# sap_flux-v10.net
KiCad netlist of a schematic drawn in EAGLE
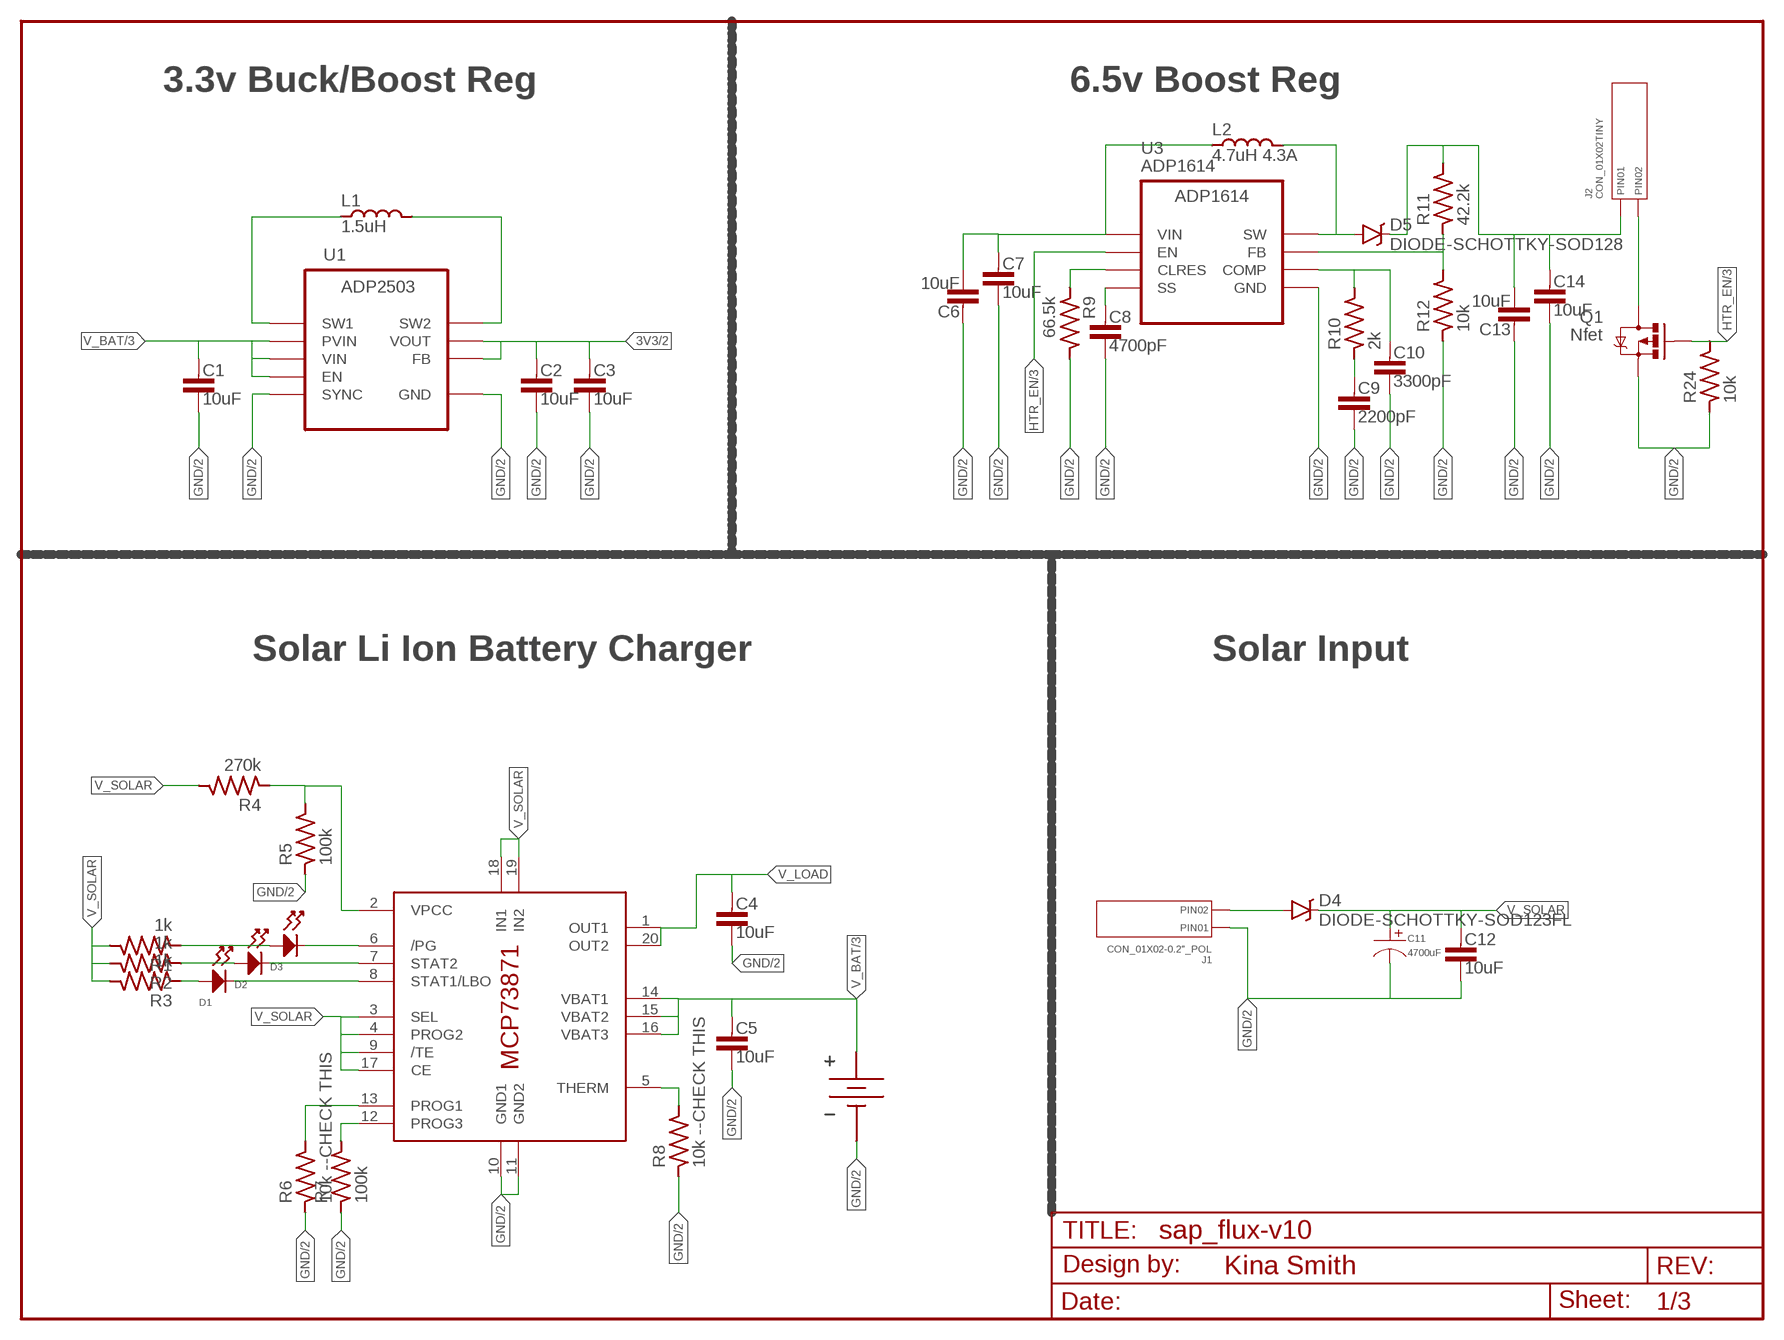
[diagram p0: schematic, sheet 1]
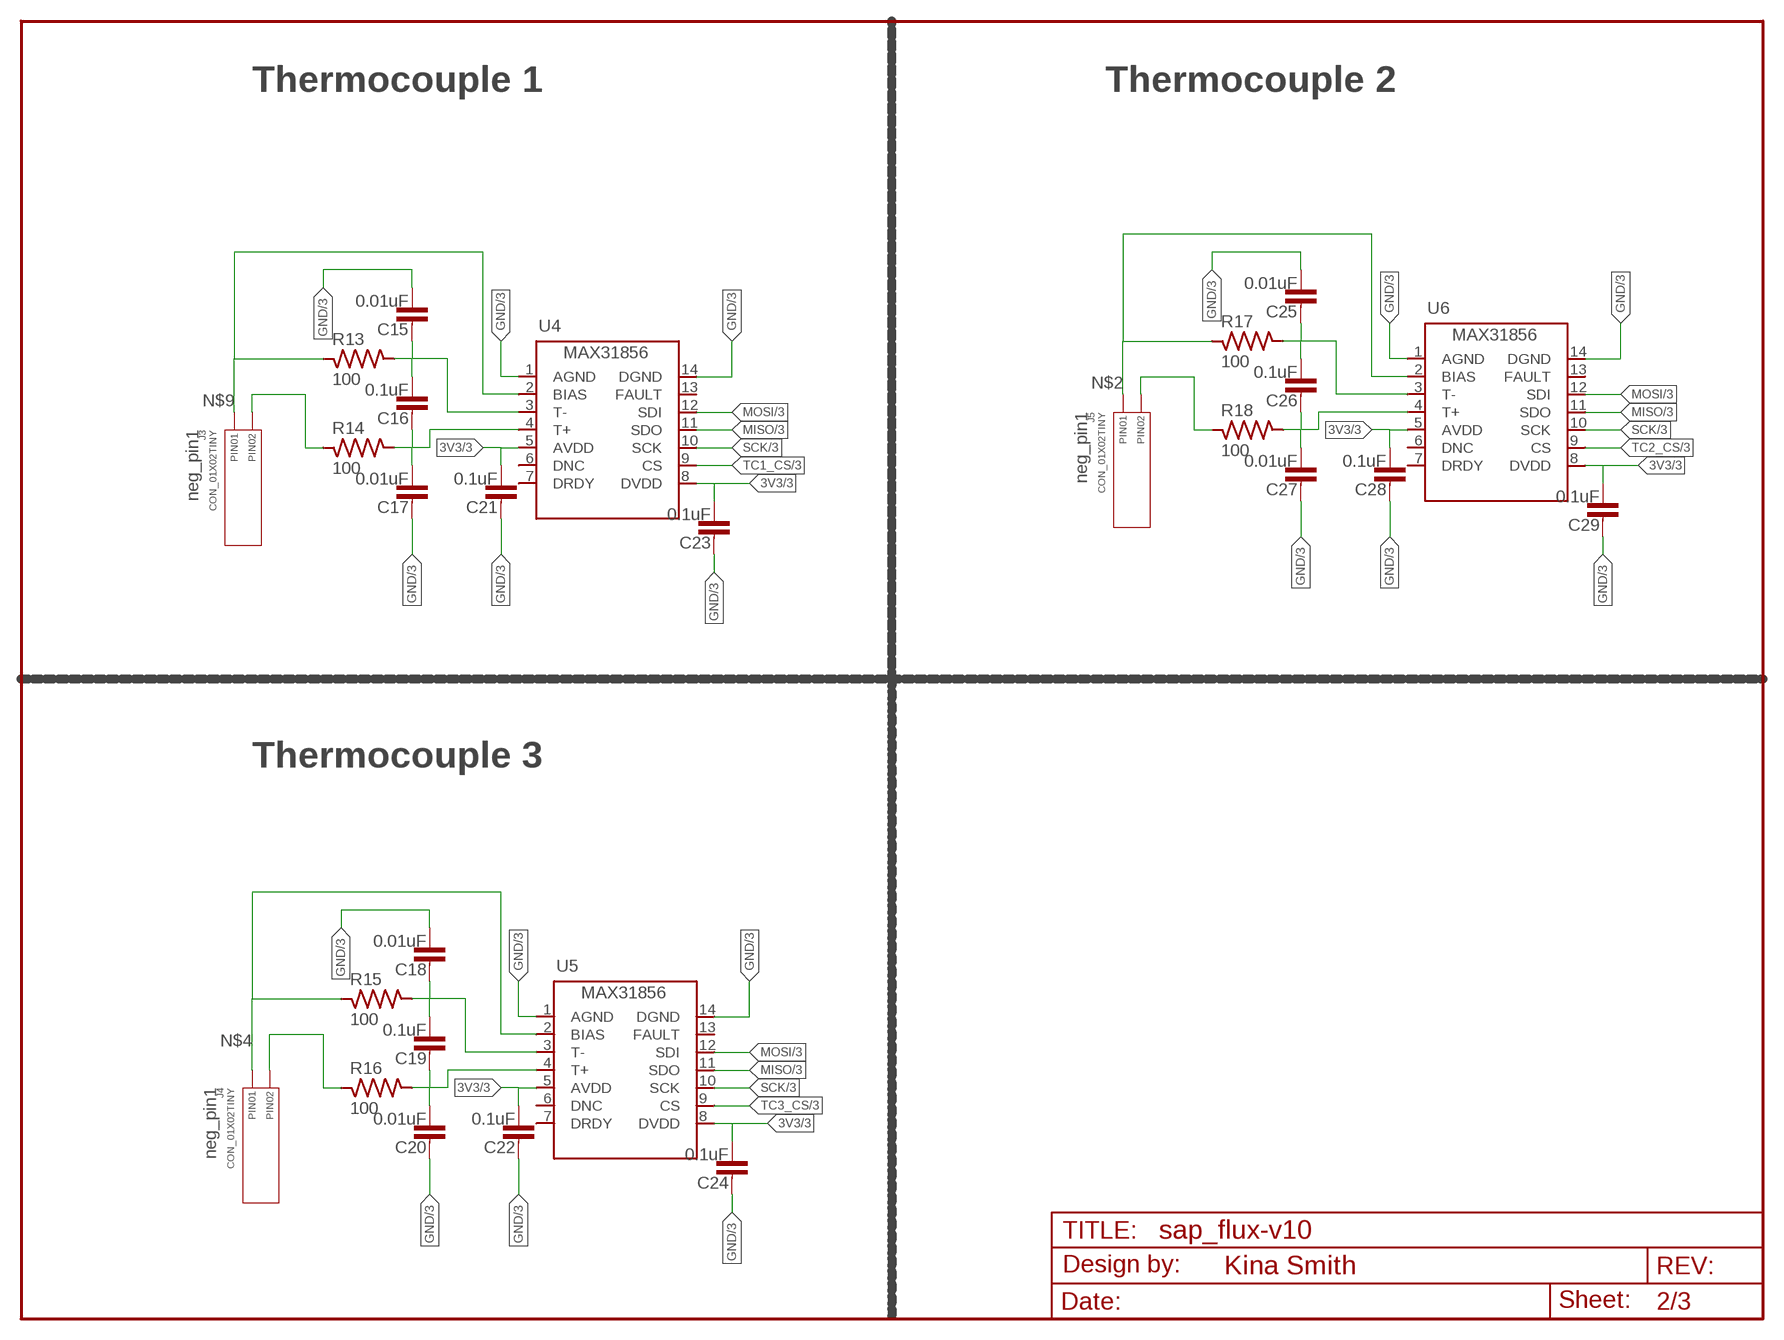
[diagram p1: schematic, sheet 2]
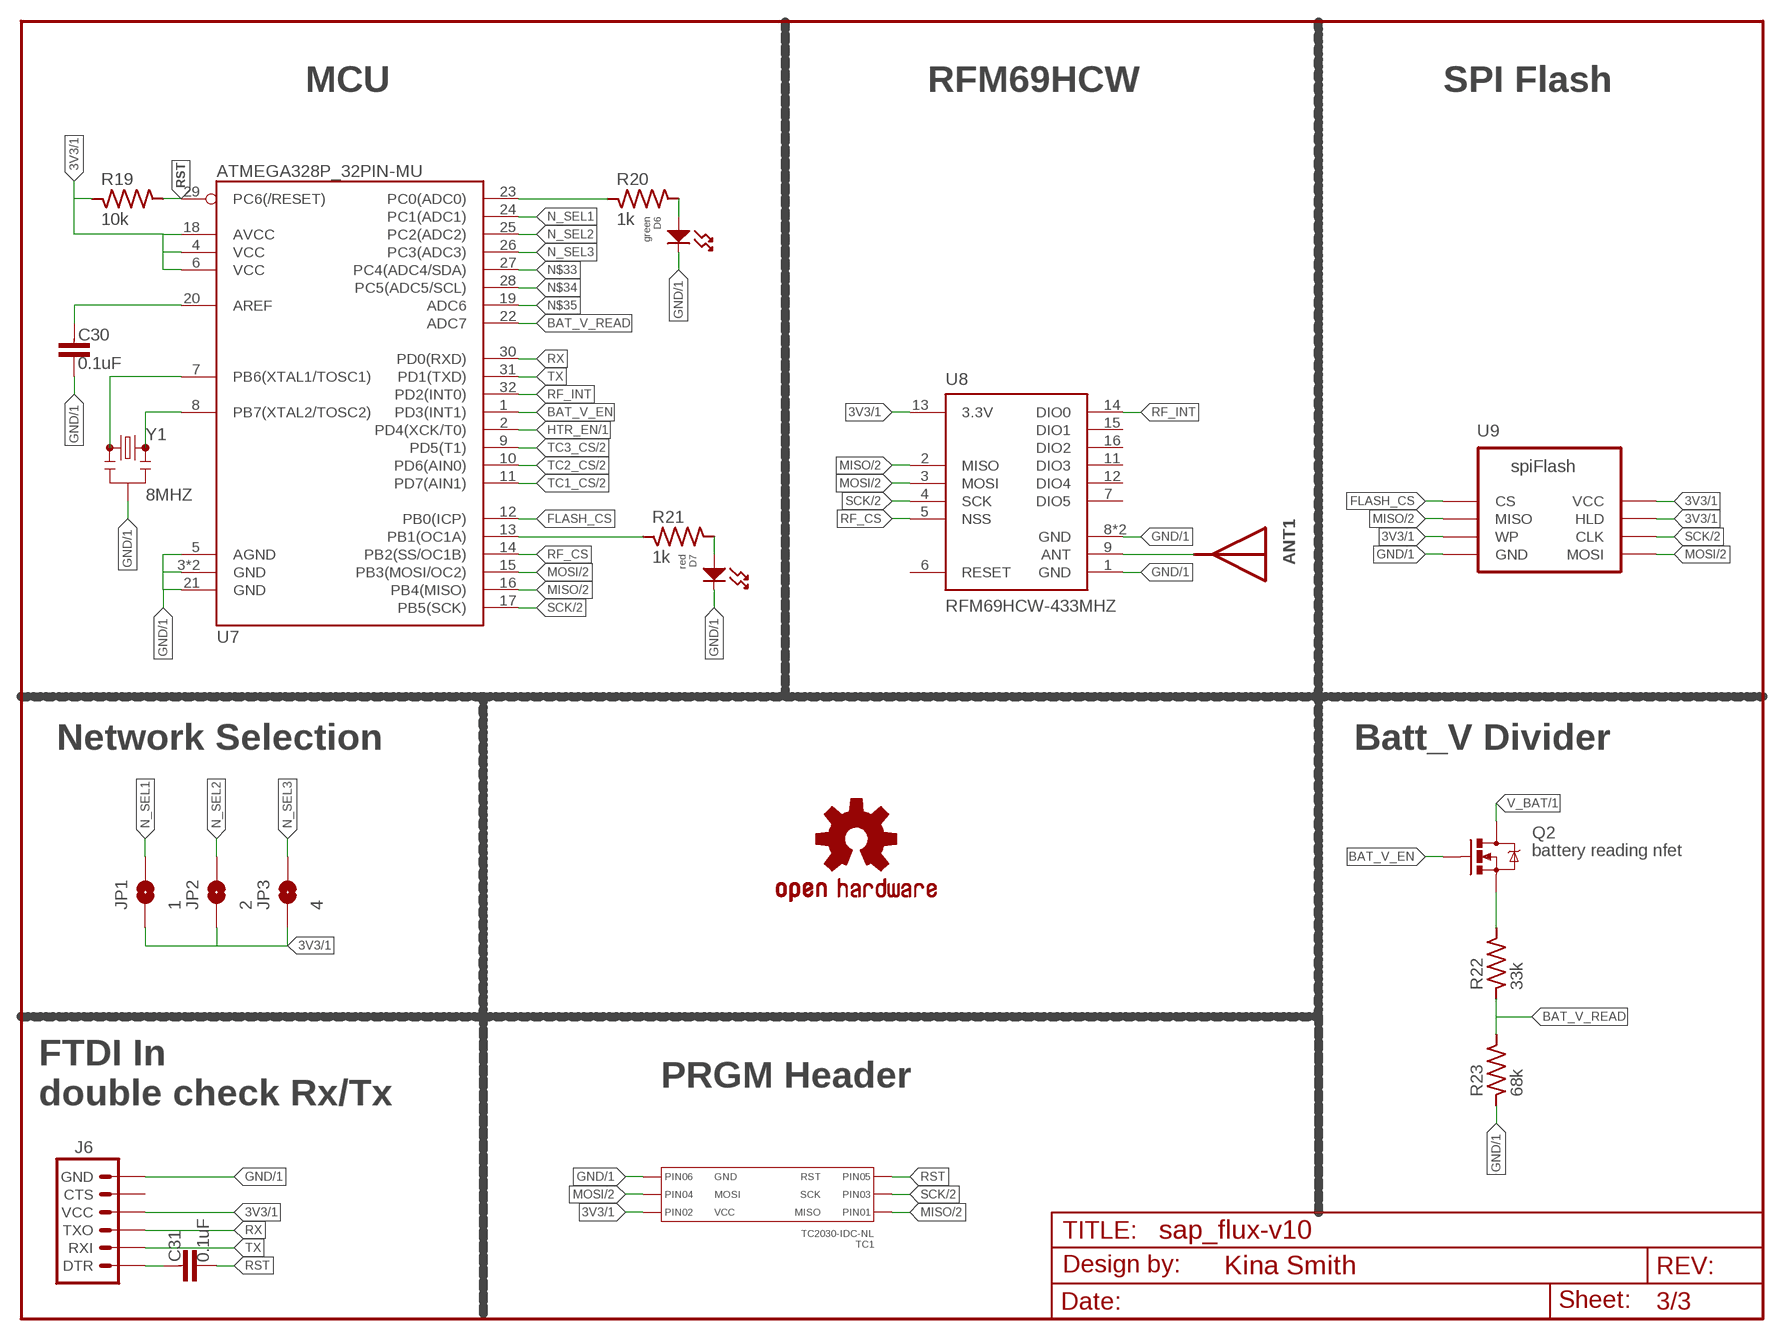
[diagram p2: schematic, sheet 3]

(export (version "E")
  (design (tool "Eeschema 10.0.6"))
  (components
    (comp (ref "ANT1")
      (value "ANTENNA-433_CHIP")
      (footprint "eagle-import:ANT_433_CHIP")
      (fields (field (name "PARTNO") "0433AT62A0020E"))
      (libsource (lib "eagle-import") (part "ANTENNA-433_CHIP"))
    )
    (comp (ref "C30")
      (value "0.1uF")
      (footprint "eagle-import:C0603-N")
      (fields (field (name "PARTNO") "CC0603KRX7R7BB104"))
      (libsource (lib "eagle-import") (part "CAPACITOR_NP0603-N"))
    )
    (comp (ref "C31")
      (value "0.1uF")
      (footprint "eagle-import:C0603-N")
      (fields (field (name "PARTNO") "CC0603KRX7R7BB104"))
      (libsource (lib "eagle-import") (part "CAPACITOR_NP0603-N"))
    )
    (comp (ref "D6")
      (value "green")
      (footprint "eagle-import:LED0603")
      (fields (field (name "HOUSEPART") "NO") (field (name "PARTNO") "LTST-C191KGKT"))
      (libsource (lib "eagle-import") (part "LED_SINGLE-0603"))
    )
    (comp (ref "D7")
      (value "red")
      (footprint "eagle-import:LED0603")
      (fields (field (name "HOUSEPART") "NO") (field (name "PARTNO") "LTST-C191KRKT"))
      (libsource (lib "eagle-import") (part "LED_SINGLE-0603"))
    )
    (comp (ref "FRAME3")
      (value "FRAME-LETTERNO_PACKAGE")
      (footprint "eagle-import:DUMMY")
      (fields (field (name "PARTNO") "NA") (field (name "DESIGNER") "Nobody"))
      (libsource (lib "eagle-import") (part "FRAME-LETTERNO_PACKAGE"))
    )
    (comp (ref "J6")
      (value "ARDUINO_SERIAL_PROGRAMPTH")
      (footprint "eagle-import:1X06")
      (fields (field (name "PARTNO") "68001-106HLF"))
      (libsource (lib "eagle-import") (part "ARDUINO_SERIAL_PROGRAMPTH"))
    )
    (comp (ref "JP1")
      (value "1")
      (footprint "eagle-import:PAD-JUMPER-2-NO_YES_SILK")
      (fields (field (name "PARTNO") "NA"))
      (libsource (lib "eagle-import") (part "JUMPER-PAD-2-NOYES_SILK"))
    )
    (comp (ref "JP2")
      (value "2")
      (footprint "eagle-import:PAD-JUMPER-2-NO_YES_SILK")
      (fields (field (name "PARTNO") "NA"))
      (libsource (lib "eagle-import") (part "JUMPER-PAD-2-NOYES_SILK"))
    )
    (comp (ref "JP3")
      (value "4")
      (footprint "eagle-import:PAD-JUMPER-2-NO_YES_SILK")
      (fields (field (name "PARTNO") "NA"))
      (libsource (lib "eagle-import") (part "JUMPER-PAD-2-NOYES_SILK"))
    )
    (comp (ref "LOGO1")
      (value "OSHW-LOGOS-COPPER")
      (footprint "eagle-import:OSHW-LOGO-S_COPPER")
      (libsource (lib "eagle-import") (part "OSHW-LOGOS-COPPER"))
    )
    (comp (ref "Q2")
      (value "battery reading nfet")
      (footprint "eagle-import:SOT23-3")
      (fields (field (name "PARTNO") "SI2312BDS-T1-GE3"))
      (libsource (lib "eagle-import") (part "MOSFET-NCHANNELSOT23-3"))
    )
    (comp (ref "R19")
      (value "10k")
      (footprint "eagle-import:R0603-N")
      (fields (field (name "PARTNO") "RC0603FR-0710KL"))
      (libsource (lib "eagle-import") (part "RESISTOR0603-N"))
    )
    (comp (ref "R20")
      (value "1k")
      (footprint "eagle-import:R0603-N")
      (fields (field (name "PARTNO") "RC0603FR-071KL"))
      (libsource (lib "eagle-import") (part "RESISTOR0603-N"))
    )
    (comp (ref "R21")
      (value "1k")
      (footprint "eagle-import:R0603-N")
      (fields (field (name "PARTNO") "RC0603FR-071KL"))
      (libsource (lib "eagle-import") (part "RESISTOR0603-N"))
    )
    (comp (ref "R22")
      (value "33k")
      (footprint "eagle-import:R0603-N")
      (fields (field (name "PARTNO") "RC0603FR-0733KL"))
      (libsource (lib "eagle-import") (part "RESISTOR0603-N"))
    )
    (comp (ref "R23")
      (value "68k")
      (footprint "eagle-import:R0603-N")
      (fields (field (name "PARTNO") "RC0603FR-0768KL"))
      (libsource (lib "eagle-import") (part "RESISTOR0603-N"))
    )
    (comp (ref "TC1")
      (value "TC2030-IDC-NL")
      (footprint "eagle-import:TC2030-IDC-NL")
      (fields (field (name "HOUSEPART") "NO") (field (name "PARTNO") "NA"))
      (libsource (lib "eagle-import") (part "CON_02X03_TC2030-IDC-NL_AVRISP"))
    )
    (comp (ref "U7")
      (value "ATMEGA328P_32PIN-MU")
      (footprint "eagle-import:MLF32_RECTPADS")
      (fields (field (name "PARTNO") "ATMEGA328P-MU"))
      (libsource (lib "eagle-import") (part "ATMEGA328P_32PIN-MU"))
    )
    (comp (ref "U8")
      (value "RFM69HCW-433MHZ")
      (footprint "eagle-import:RFM69HCW-XXXS2")
      (fields (field (name "PARTNO") "COM-13910"))
      (libsource (lib "eagle-import") (part "RFM69HCW-433MHZ"))
    )
    (comp (ref "U9")
      (value "WINBOND_FLASH_4MBIT-SOIC")
      (footprint "eagle-import:SOIC8")
      (fields (field (name "PARTNO") "W25X40CLSNIG"))
      (libsource (lib "eagle-import") (part "WINBOND_FLASH_4MBIT-SOIC"))
    )
    (comp (ref "Y1")
      (value "8MHZ")
      (footprint "eagle-import:RESONATOR-SMD")
      (fields (field (name "PARTNO") "CSTCE8M00G55-R0"))
      (libsource (lib "eagle-import") (part "RESONATOR8MHZ"))
    )
    (comp (ref "BATT1")
      (value "BATTERY_HOLDER-18650_CLIP")
      (footprint "eagle-import:BAT_18650_CLIP")
      (fields (field (name "PARTNO") "54"))
      (libsource (lib "eagle-import") (part "BATTERY_HOLDER-18650_CLIP"))
    )
    (comp (ref "C1")
      (value "10uF")
      (footprint "eagle-import:C0805-N")
      (fields (field (name "PARTNO") "GRM21BR61C106KE15K"))
      (libsource (lib "eagle-import") (part "CAPACITOR_NP0805-N"))
    )
    (comp (ref "C2")
      (value "10uF")
      (footprint "eagle-import:C0805-N")
      (fields (field (name "PARTNO") "GRM21BR61C106KE15K"))
      (libsource (lib "eagle-import") (part "CAPACITOR_NP0805-N"))
    )
    (comp (ref "C3")
      (value "10uF")
      (footprint "eagle-import:C0805-N")
      (fields (field (name "PARTNO") "GRM21BR61C106KE15K"))
      (libsource (lib "eagle-import") (part "CAPACITOR_NP0805-N"))
    )
    (comp (ref "C4")
      (value "10uF")
      (footprint "eagle-import:C0805-N")
      (fields (field (name "PARTNO") "GRM21BR61C106KE15K"))
      (libsource (lib "eagle-import") (part "CAPACITOR_NP0805-N"))
    )
    (comp (ref "C5")
      (value "10uF")
      (footprint "eagle-import:C0805-N")
      (fields (field (name "PARTNO") "GRM21BR61C106KE15K"))
      (libsource (lib "eagle-import") (part "CAPACITOR_NP0805-N"))
    )
    (comp (ref "C6")
      (value "10uF")
      (footprint "eagle-import:C0805-N")
      (fields (field (name "PARTNO") "GRM21BR61C106KE15K"))
      (libsource (lib "eagle-import") (part "CAPACITOR_NP0805-N"))
    )
    (comp (ref "C7")
      (value "10uF")
      (footprint "eagle-import:C0805-N")
      (fields (field (name "PARTNO") "GRM21BR61C106KE15K"))
      (libsource (lib "eagle-import") (part "CAPACITOR_NP0805-N"))
    )
    (comp (ref "C8")
      (value "4700pF")
      (footprint "eagle-import:C0603-N")
      (fields (field (name "PARTNO") "GRM188R71C472KA01D"))
      (libsource (lib "eagle-import") (part "CAPACITOR_NP0603-N"))
    )
    (comp (ref "C9")
      (value "2200pF")
      (footprint "eagle-import:C0603-N")
      (fields (field (name "PARTNO") "GRM188R71C222KA01D"))
      (libsource (lib "eagle-import") (part "CAPACITOR_NP0603-N"))
    )
    (comp (ref "C10")
      (value "3300pF")
      (footprint "eagle-import:C0603-N")
      (fields (field (name "PARTNO") "C0603C332K4RACTU"))
      (libsource (lib "eagle-import") (part "CAPACITOR_NP0603-N"))
    )
    (comp (ref "C11")
      (value "4700uF")
      (footprint "eagle-import:CP_TH_5MM")
      (fields (field (name "PARTNO") "ECA-1AM472"))
      (libsource (lib "eagle-import") (part "CAPACITOR_P-TH_5MM"))
    )
    (comp (ref "C12")
      (value "10uF")
      (footprint "eagle-import:C0805-N")
      (fields (field (name "PARTNO") "GRM21BR61C106KE15K"))
      (libsource (lib "eagle-import") (part "CAPACITOR_NP0805-N"))
    )
    (comp (ref "C13")
      (value "10uF")
      (footprint "eagle-import:C0805-N")
      (fields (field (name "PARTNO") "GRM21BR61C106KE15K"))
      (libsource (lib "eagle-import") (part "CAPACITOR_NP0805-N"))
    )
    (comp (ref "C14")
      (value "10uF")
      (footprint "eagle-import:C0805-N")
      (fields (field (name "PARTNO") "GRM21BR61C106KE15K"))
      (libsource (lib "eagle-import") (part "CAPACITOR_NP0805-N"))
    )
    (comp (ref "D1")
      (value "LED_SINGLE-0603")
      (footprint "eagle-import:LED0603")
      (fields (field (name "HOUSEPART") "NO") (field (name "PARTNO") "LTST-C191KRKT"))
      (libsource (lib "eagle-import") (part "LED_SINGLE-0603"))
    )
    (comp (ref "D2")
      (value "LED_SINGLE-0603")
      (footprint "eagle-import:LED0603")
      (fields (field (name "HOUSEPART") "NO") (field (name "PARTNO") "LTST-C191KRKT"))
      (libsource (lib "eagle-import") (part "LED_SINGLE-0603"))
    )
    (comp (ref "D3")
      (value "LED_SINGLE-0603")
      (footprint "eagle-import:LED0603")
      (fields (field (name "HOUSEPART") "NO") (field (name "PARTNO") "LTST-C191KRKT"))
      (libsource (lib "eagle-import") (part "LED_SINGLE-0603"))
    )
    (comp (ref "D4")
      (value "DIODE-SCHOTTKY-SOD123FL")
      (footprint "eagle-import:SOD-123FL")
      (fields (field (name "PARTNO") "MBR120VLSFT1G"))
      (libsource (lib "eagle-import") (part "DIODE-SCHOTTKY-SOD123FL"))
    )
    (comp (ref "D5")
      (value "DIODE-SCHOTTKY-SOD128")
      (footprint "eagle-import:SOD128")
      (fields (field (name "PARTNO") "CMS05(TE12L,Q,M)"))
      (libsource (lib "eagle-import") (part "DIODE-SCHOTTKY-SOD128"))
    )
    (comp (ref "FRAME1")
      (value "FRAME-LETTER")
      (footprint "eagle-import:CREATIVE_COMMONS")
      (fields (field (name "PARTNO") "NA"))
      (libsource (lib "eagle-import") (part "FRAME-LETTER"))
    )
    (comp (ref "J1")
      (value "CON_01X02-0.2\"_POL")
      (footprint "eagle-import:1X02_SCREWTERM_0.2IN")
      (fields (field (name "PARTNO") "0398890042"))
      (libsource (lib "eagle-import") (part "CON_01X02-0.2{dblquote}_POL"))
    )
    (comp (ref "J2")
      (value "CON_01X02TINY")
      (footprint "eagle-import:1X02_TINY")
      (libsource (lib "eagle-import") (part "CON_01X02TINY"))
    )
    (comp (ref "L1")
      (value "1.5uH")
      (footprint "eagle-import:L3030")
      (fields (field (name "PARTNO") "NR3015T1R5N"))
      (libsource (lib "eagle-import") (part "INDUCTOR3030"))
    )
    (comp (ref "L2")
      (value "4.7uH 4.3A")
      (footprint "eagle-import:L8080")
      (fields (field (name "PARTNO") "NRS8040T100MJGJ"))
      (libsource (lib "eagle-import") (part "INDUCTOR8080"))
    )
    (comp (ref "Q1")
      (value "Nfet")
      (footprint "eagle-import:SOT23-3")
      (fields (field (name "PARTNO") "DMN2075U-7"))
      (libsource (lib "eagle-import") (part "MOSFET-PCHANNELSOT23-3"))
    )
    (comp (ref "R1")
      (value "1k")
      (footprint "eagle-import:R0603-N")
      (fields (field (name "PARTNO") "RC0603FR-071KL"))
      (libsource (lib "eagle-import") (part "RESISTOR0603-N"))
    )
    (comp (ref "R2")
      (value "1k")
      (footprint "eagle-import:R0603-N")
      (fields (field (name "PARTNO") "RC0603FR-071KL"))
      (libsource (lib "eagle-import") (part "RESISTOR0603-N"))
    )
    (comp (ref "R3")
      (value "1k")
      (footprint "eagle-import:R0603-N")
      (fields (field (name "PARTNO") "RC0603FR-071KL"))
      (libsource (lib "eagle-import") (part "RESISTOR0603-N"))
    )
    (comp (ref "R4")
      (value "270k")
      (footprint "eagle-import:R0603-N")
      (fields (field (name "PARTNO") "RC0603FR-07270KL"))
      (libsource (lib "eagle-import") (part "RESISTOR0603-N"))
    )
    (comp (ref "R5")
      (value "100k")
      (footprint "eagle-import:R0603-N")
      (fields (field (name "PARTNO") "RC0603FR-07100KL"))
      (libsource (lib "eagle-import") (part "RESISTOR0603-N"))
    )
    (comp (ref "R6")
      (value "10k --CHECK THIS")
      (footprint "eagle-import:R0603-N")
      (fields (field (name "PARTNO") "RC0603FR-0710KL"))
      (libsource (lib "eagle-import") (part "RESISTOR0603-N"))
    )
    (comp (ref "R7")
      (value "100k")
      (footprint "eagle-import:R0603-N")
      (fields (field (name "PARTNO") "RC0603FR-07100KL"))
      (libsource (lib "eagle-import") (part "RESISTOR0603-N"))
    )
    (comp (ref "R8")
      (value "10k --CHECK THIS")
      (footprint "eagle-import:R0603-N")
      (fields (field (name "PARTNO") "RC0603FR-0710KL"))
      (libsource (lib "eagle-import") (part "RESISTOR0603-N"))
    )
    (comp (ref "R9")
      (value "66.5k")
      (footprint "eagle-import:R0603-N")
      (fields (field (name "PARTNO") "RC0603FR-0766K5L"))
      (libsource (lib "eagle-import") (part "RESISTOR0603-N"))
    )
    (comp (ref "R10")
      (value "2k")
      (footprint "eagle-import:R0603-N")
      (fields (field (name "PARTNO") "RC0603FR-072KL"))
      (libsource (lib "eagle-import") (part "RESISTOR0603-N"))
    )
    (comp (ref "R11")
      (value "42.2k")
      (footprint "eagle-import:R0603-N")
      (fields (field (name "PARTNO") "RC0603FR-0742K2L"))
      (libsource (lib "eagle-import") (part "RESISTOR0603-N"))
    )
    (comp (ref "R12")
      (value "10k")
      (footprint "eagle-import:R0603-N")
      (fields (field (name "PARTNO") "RC0603FR-0710KL"))
      (libsource (lib "eagle-import") (part "RESISTOR0603-N"))
    )
    (comp (ref "R24")
      (value "10k")
      (footprint "eagle-import:R0603-N")
      (fields (field (name "PARTNO") "RC0603FR-0710KL"))
      (libsource (lib "eagle-import") (part "RESISTOR0603-N"))
    )
    (comp (ref "U1")
      (value "ADP2503")
      (footprint "eagle-import:DFN300X300X80-11N")
      (fields (field (name "PARTNO") "ADP2503ACPZ-3.3-R7 ") (field (name "PARTNO_1") "ADP2503ACPZ-3.3-R7"))
      (libsource (lib "eagle-import") (part "ADP2503"))
    )
    (comp (ref "U2")
      (value "MCP73871")
      (footprint "eagle-import:QFN20")
      (fields (field (name "PARTNO") "MCP73871-2AAI/ML-ND"))
      (libsource (lib "eagle-import") (part "MCP73871"))
    )
    (comp (ref "U3")
      (value "ADP1614")
      (footprint "eagle-import:DFN300X300X80-11N")
      (fields (field (name "PARTNO") "ADP1614ACPZ-R7") (field (name "PARTNO_1") "ADP1614ACPZ-650-R7"))
      (libsource (lib "eagle-import") (part "ADP1614"))
    )
    (comp (ref "C15")
      (value "0.01uF")
      (footprint "eagle-import:C0603-N")
      (fields (field (name "PARTNO") "GRM188R71C103KA01D"))
      (libsource (lib "eagle-import") (part "CAPACITOR_NP0603-N"))
    )
    (comp (ref "C16")
      (value "0.1uF")
      (footprint "eagle-import:C0603-N")
      (fields (field (name "PARTNO") "CC0603KRX7R7BB104"))
      (libsource (lib "eagle-import") (part "CAPACITOR_NP0603-N"))
    )
    (comp (ref "C17")
      (value "0.01uF")
      (footprint "eagle-import:C0603-N")
      (fields (field (name "PARTNO") "GRM188R71C103KA01D"))
      (libsource (lib "eagle-import") (part "CAPACITOR_NP0603-N"))
    )
    (comp (ref "C18")
      (value "0.01uF")
      (footprint "eagle-import:C0603-N")
      (fields (field (name "PARTNO") "GRM188R71C103KA01D"))
      (libsource (lib "eagle-import") (part "CAPACITOR_NP0603-N"))
    )
    (comp (ref "C19")
      (value "0.1uF")
      (footprint "eagle-import:C0603-N")
      (fields (field (name "PARTNO") "CC0603KRX7R7BB104"))
      (libsource (lib "eagle-import") (part "CAPACITOR_NP0603-N"))
    )
    (comp (ref "C20")
      (value "0.01uF")
      (footprint "eagle-import:C0603-N")
      (fields (field (name "PARTNO") "GRM188R71C103KA01D"))
      (libsource (lib "eagle-import") (part "CAPACITOR_NP0603-N"))
    )
    (comp (ref "C21")
      (value "0.1uF")
      (footprint "eagle-import:C0603-N")
      (fields (field (name "PARTNO") "CC0603KRX7R7BB104"))
      (libsource (lib "eagle-import") (part "CAPACITOR_NP0603-N"))
    )
    (comp (ref "C22")
      (value "0.1uF")
      (footprint "eagle-import:C0603-N")
      (fields (field (name "PARTNO") "CC0603KRX7R7BB104"))
      (libsource (lib "eagle-import") (part "CAPACITOR_NP0603-N"))
    )
    (comp (ref "C23")
      (value "0.1uF")
      (footprint "eagle-import:C0603-N")
      (fields (field (name "PARTNO") "CC0603KRX7R7BB104"))
      (libsource (lib "eagle-import") (part "CAPACITOR_NP0603-N"))
    )
    (comp (ref "C24")
      (value "0.1uF")
      (footprint "eagle-import:C0603-N")
      (fields (field (name "PARTNO") "CC0603KRX7R7BB104"))
      (libsource (lib "eagle-import") (part "CAPACITOR_NP0603-N"))
    )
    (comp (ref "C25")
      (value "0.01uF")
      (footprint "eagle-import:C0603-N")
      (fields (field (name "PARTNO") "GRM188R71C103KA01D"))
      (libsource (lib "eagle-import") (part "CAPACITOR_NP0603-N"))
    )
    (comp (ref "C26")
      (value "0.1uF")
      (footprint "eagle-import:C0603-N")
      (fields (field (name "PARTNO") "CC0603KRX7R7BB104"))
      (libsource (lib "eagle-import") (part "CAPACITOR_NP0603-N"))
    )
    (comp (ref "C27")
      (value "0.01uF")
      (footprint "eagle-import:C0603-N")
      (fields (field (name "PARTNO") "GRM188R71C103KA01D"))
      (libsource (lib "eagle-import") (part "CAPACITOR_NP0603-N"))
    )
    (comp (ref "C28")
      (value "0.1uF")
      (footprint "eagle-import:C0603-N")
      (fields (field (name "PARTNO") "CC0603KRX7R7BB104"))
      (libsource (lib "eagle-import") (part "CAPACITOR_NP0603-N"))
    )
    (comp (ref "C29")
      (value "0.1uF")
      (footprint "eagle-import:C0603-N")
      (fields (field (name "PARTNO") "CC0603KRX7R7BB104"))
      (libsource (lib "eagle-import") (part "CAPACITOR_NP0603-N"))
    )
    (comp (ref "FRAME2")
      (value "FRAME-LETTERNO_PACKAGE")
      (footprint "eagle-import:DUMMY")
      (fields (field (name "PARTNO") "NA") (field (name "DESIGNER") "Nobody"))
      (libsource (lib "eagle-import") (part "FRAME-LETTERNO_PACKAGE"))
    )
    (comp (ref "J3")
      (value "CON_01X02TINY")
      (footprint "eagle-import:1X02_TINY")
      (fields (field (name "NOTE") "neg_pin1"))
      (libsource (lib "eagle-import") (part "CON_01X02TINY"))
    )
    (comp (ref "J4")
      (value "CON_01X02TINY")
      (footprint "eagle-import:1X02_TINY")
      (fields (field (name "NOTE") "neg_pin1"))
      (libsource (lib "eagle-import") (part "CON_01X02TINY"))
    )
    (comp (ref "J5")
      (value "CON_01X02TINY")
      (footprint "eagle-import:1X02_TINY")
      (fields (field (name "NOTE") "neg_pin1"))
      (libsource (lib "eagle-import") (part "CON_01X02TINY"))
    )
    (comp (ref "R13")
      (value "100")
      (footprint "eagle-import:R0603-N")
      (fields (field (name "PARTNO") "RC0603FR-07100RL"))
      (libsource (lib "eagle-import") (part "RESISTOR0603-N"))
    )
    (comp (ref "R14")
      (value "100")
      (footprint "eagle-import:R0603-N")
      (fields (field (name "PARTNO") "RC0603FR-07100RL"))
      (libsource (lib "eagle-import") (part "RESISTOR0603-N"))
    )
    (comp (ref "R15")
      (value "100")
      (footprint "eagle-import:R0603-N")
      (fields (field (name "PARTNO") "RC0603FR-07100RL"))
      (libsource (lib "eagle-import") (part "RESISTOR0603-N"))
    )
    (comp (ref "R16")
      (value "100")
      (footprint "eagle-import:R0603-N")
      (fields (field (name "PARTNO") "RC0603FR-07100RL"))
      (libsource (lib "eagle-import") (part "RESISTOR0603-N"))
    )
    (comp (ref "R17")
      (value "100")
      (footprint "eagle-import:R0603-N")
      (fields (field (name "PARTNO") "RC0603FR-07100RL"))
      (libsource (lib "eagle-import") (part "RESISTOR0603-N"))
    )
    (comp (ref "R18")
      (value "100")
      (footprint "eagle-import:R0603-N")
      (fields (field (name "PARTNO") "RC0603FR-07100RL"))
      (libsource (lib "eagle-import") (part "RESISTOR0603-N"))
    )
    (comp (ref "U4")
      (value "MAX31856MUD+")
      (footprint "eagle-import:TSSOP14")
      (libsource (lib "eagle-import") (part "MAX31856MUD+"))
    )
    (comp (ref "U5")
      (value "MAX31856MUD+")
      (footprint "eagle-import:TSSOP14")
      (libsource (lib "eagle-import") (part "MAX31856MUD+"))
    )
    (comp (ref "U6")
      (value "MAX31856MUD+")
      (footprint "eagle-import:TSSOP14")
      (libsource (lib "eagle-import") (part "MAX31856MUD+"))
    )
  )
  (nets
    (net (code "1") (name "3V3") (class "Default")
      (node (ref "C2") (pin "1") (pinfunction "1_1") (pintype "passive"))
      (node (ref "C21") (pin "2") (pinfunction "2_2") (pintype "passive"))
      (node (ref "C22") (pin "2") (pinfunction "2_2") (pintype "passive"))
      (node (ref "C23") (pin "2") (pinfunction "2_2") (pintype "passive"))
      (node (ref "C24") (pin "2") (pinfunction "2_2") (pintype "passive"))
      (node (ref "C28") (pin "2") (pinfunction "2_2") (pintype "passive"))
      (node (ref "C29") (pin "2") (pinfunction "2_2") (pintype "passive"))
      (node (ref "C3") (pin "1") (pinfunction "1_1") (pintype "passive"))
      (node (ref "J6") (pin "4") (pinfunction "VCC_4") (pintype "passive"))
      (node (ref "JP1") (pin "1") (pinfunction "1_1") (pintype "passive"))
      (node (ref "JP2") (pin "1") (pinfunction "1_1") (pintype "passive"))
      (node (ref "JP3") (pin "1") (pinfunction "1_1") (pintype "passive"))
      (node (ref "R19") (pin "1") (pinfunction "P$1_1") (pintype "passive"))
      (node (ref "TC1") (pin "P$2") (pinfunction "PIN2_P$2") (pintype "bidirectional"))
      (node (ref "U1") (pin "1") (pinfunction "VOUT_1") (pintype "bidirectional"))
      (node (ref "U1") (pin "10") (pinfunction "FB_10") (pintype "bidirectional"))
      (node (ref "U4") (pin "5") (pinfunction "AVDD_5") (pintype "bidirectional"))
      (node (ref "U4") (pin "8") (pinfunction "DVDD_8") (pintype "bidirectional"))
      (node (ref "U5") (pin "5") (pinfunction "AVDD_5") (pintype "bidirectional"))
      (node (ref "U5") (pin "8") (pinfunction "DVDD_8") (pintype "bidirectional"))
      (node (ref "U6") (pin "5") (pinfunction "AVDD_5") (pintype "bidirectional"))
      (node (ref "U6") (pin "8") (pinfunction "DVDD_8") (pintype "bidirectional"))
      (node (ref "U7") (pin "18") (pinfunction "AVCC_18") (pintype "bidirectional"))
      (node (ref "U7") (pin "4") (pinfunction "VCC_4") (pintype "bidirectional"))
      (node (ref "U7") (pin "6") (pinfunction "VCC_6") (pintype "bidirectional"))
      (node (ref "U8") (pin "13") (pinfunction "3.3V_13") (pintype "power_in"))
      (node (ref "U9") (pin "3") (pinfunction "WP_3") (pintype "bidirectional"))
      (node (ref "U9") (pin "7") (pinfunction "HLD_7") (pintype "bidirectional"))
      (node (ref "U9") (pin "8") (pinfunction "VCC_8") (pintype "bidirectional"))
    )
    (net (code "2") (name "BAT_V_EN") (class "Default")
      (node (ref "Q2") (pin "1") (pinfunction "G_1") (pintype "passive"))
      (node (ref "U7") (pin "1") (pinfunction "PD3(INT1)_1") (pintype "bidirectional"))
    )
    (net (code "3") (name "BAT_V_READ") (class "Default")
      (node (ref "R22") (pin "1") (pinfunction "P$1_1") (pintype "passive"))
      (node (ref "R23") (pin "2") (pinfunction "P$2_2") (pintype "passive"))
      (node (ref "U7") (pin "22") (pinfunction "ADC7_22") (pintype "bidirectional"))
    )
    (net (code "4") (name "FLASH_CS") (class "Default")
      (node (ref "U7") (pin "12") (pinfunction "PB0(ICP)_12") (pintype "bidirectional"))
      (node (ref "U9") (pin "1") (pinfunction "CS_1") (pintype "bidirectional"))
    )
    (net (code "5") (name "GND") (class "Default")
      (node (ref "BATT1") (pin "NEG_1") (pinfunction "GND_NEG_1") (pintype "bidirectional"))
      (node (ref "BATT1") (pin "NEG_2") (pinfunction "GND_NEG_2") (pintype "bidirectional"))
      (node (ref "BATT1") (pin "NEG_3") (pinfunction "GND_NEG_3") (pintype "bidirectional"))
      (node (ref "C1") (pin "2") (pinfunction "2_2") (pintype "passive"))
      (node (ref "C10") (pin "2") (pinfunction "2_2") (pintype "passive"))
      (node (ref "C11") (pin "NEG") (pinfunction "NET_NEG") (pintype "passive"))
      (node (ref "C12") (pin "2") (pinfunction "2_2") (pintype "passive"))
      (node (ref "C13") (pin "1") (pinfunction "1_1") (pintype "passive"))
      (node (ref "C14") (pin "2") (pinfunction "2_2") (pintype "passive"))
      (node (ref "C15") (pin "2") (pinfunction "2_2") (pintype "passive"))
      (node (ref "C17") (pin "1") (pinfunction "1_1") (pintype "passive"))
      (node (ref "C18") (pin "2") (pinfunction "2_2") (pintype "passive"))
      (node (ref "C2") (pin "2") (pinfunction "2_2") (pintype "passive"))
      (node (ref "C20") (pin "1") (pinfunction "1_1") (pintype "passive"))
      (node (ref "C21") (pin "1") (pinfunction "1_1") (pintype "passive"))
      (node (ref "C22") (pin "1") (pinfunction "1_1") (pintype "passive"))
      (node (ref "C23") (pin "1") (pinfunction "1_1") (pintype "passive"))
      (node (ref "C24") (pin "1") (pinfunction "1_1") (pintype "passive"))
      (node (ref "C25") (pin "2") (pinfunction "2_2") (pintype "passive"))
      (node (ref "C27") (pin "1") (pinfunction "1_1") (pintype "passive"))
      (node (ref "C28") (pin "1") (pinfunction "1_1") (pintype "passive"))
      (node (ref "C29") (pin "1") (pinfunction "1_1") (pintype "passive"))
      (node (ref "C3") (pin "2") (pinfunction "2_2") (pintype "passive"))
      (node (ref "C30") (pin "2") (pinfunction "2_2") (pintype "passive"))
      (node (ref "C4") (pin "2") (pinfunction "2_2") (pintype "passive"))
      (node (ref "C5") (pin "2") (pinfunction "2_2") (pintype "passive"))
      (node (ref "C6") (pin "1") (pinfunction "1_1") (pintype "passive"))
      (node (ref "C7") (pin "2") (pinfunction "2_2") (pintype "passive"))
      (node (ref "C8") (pin "2") (pinfunction "2_2") (pintype "passive"))
      (node (ref "C9") (pin "2") (pinfunction "2_2") (pintype "passive"))
      (node (ref "D6") (pin "CATHODE") (pinfunction "CATHODE_CATHODE") (pintype "power_in"))
      (node (ref "D7") (pin "CATHODE") (pinfunction "CATHODE_CATHODE") (pintype "power_in"))
      (node (ref "J1") (pin "NEG") (pinfunction "PIN1_NEG") (pintype "bidirectional"))
      (node (ref "J6") (pin "6") (pinfunction "GND_6") (pintype "passive"))
      (node (ref "Q1") (pin "2") (pinfunction "S_2") (pintype "passive"))
      (node (ref "R12") (pin "1") (pinfunction "P$1_1") (pintype "passive"))
      (node (ref "R23") (pin "1") (pinfunction "P$1_1") (pintype "passive"))
      (node (ref "R24") (pin "1") (pinfunction "P$1_1") (pintype "passive"))
      (node (ref "R5") (pin "1") (pinfunction "P$1_1") (pintype "passive"))
      (node (ref "R6") (pin "1") (pinfunction "P$1_1") (pintype "passive"))
      (node (ref "R7") (pin "1") (pinfunction "P$1_1") (pintype "passive"))
      (node (ref "R8") (pin "1") (pinfunction "P$1_1") (pintype "passive"))
      (node (ref "R9") (pin "2") (pinfunction "P$2_2") (pintype "passive"))
      (node (ref "TC1") (pin "P$6") (pinfunction "PIN6_P$6") (pintype "bidirectional"))
      (node (ref "U1") (pin "11") (pinfunction "GND_11") (pintype "bidirectional"))
      (node (ref "U1") (pin "3") (pinfunction "GND_3") (pintype "bidirectional"))
      (node (ref "U1") (pin "7") (pinfunction "SYNC_7") (pintype "bidirectional"))
      (node (ref "U1") (pin "9") (pinfunction "GND_9") (pintype "bidirectional"))
      (node (ref "U2") (pin "10") (pinfunction "GND1_10") (pintype "power_in"))
      (node (ref "U2") (pin "11") (pinfunction "GND2_11") (pintype "power_in"))
      (node (ref "U3") (pin "11") (pinfunction "GND_11") (pintype "bidirectional"))
      (node (ref "U3") (pin "4") (pinfunction "GND_4") (pintype "bidirectional"))
      (node (ref "U3") (pin "5") (pinfunction "GND_5") (pintype "bidirectional"))
      (node (ref "U4") (pin "1") (pinfunction "AGND_1") (pintype "bidirectional"))
      (node (ref "U4") (pin "14") (pinfunction "DGND_14") (pintype "bidirectional"))
      (node (ref "U5") (pin "1") (pinfunction "AGND_1") (pintype "bidirectional"))
      (node (ref "U5") (pin "14") (pinfunction "DGND_14") (pintype "bidirectional"))
      (node (ref "U6") (pin "1") (pinfunction "AGND_1") (pintype "bidirectional"))
      (node (ref "U6") (pin "14") (pinfunction "DGND_14") (pintype "bidirectional"))
      (node (ref "U7") (pin "21") (pinfunction "GND_21") (pintype "bidirectional"))
      (node (ref "U7") (pin "3") (pinfunction "GND_3") (pintype "bidirectional"))
      (node (ref "U7") (pin "5") (pinfunction "AGND_5") (pintype "bidirectional"))
      (node (ref "U7") (pin "PAD") (pinfunction "GND_PAD") (pintype "bidirectional"))
      (node (ref "U8") (pin "1") (pinfunction "GND_1") (pintype "power_in"))
      (node (ref "U8") (pin "10") (pinfunction "GND_10") (pintype "power_in"))
      (node (ref "U8") (pin "8") (pinfunction "GND_8") (pintype "power_in"))
      (node (ref "U9") (pin "4") (pinfunction "GND_4") (pintype "bidirectional"))
      (node (ref "Y1") (pin "2") (pinfunction "2_2") (pintype "passive"))
    )
    (net (code "6") (name "HTR_EN") (class "Default")
      (node (ref "Q1") (pin "1") (pinfunction "G_1") (pintype "passive"))
      (node (ref "R24") (pin "2") (pinfunction "P$2_2") (pintype "passive"))
      (node (ref "U3") (pin "3") (pinfunction "EN_3") (pintype "bidirectional"))
      (node (ref "U7") (pin "2") (pinfunction "PD4(XCK/T0)_2") (pintype "bidirectional"))
    )
    (net (code "7") (name "MISO") (class "Default")
      (node (ref "TC1") (pin "P$1") (pinfunction "PIN1_P$1") (pintype "bidirectional"))
      (node (ref "U4") (pin "11") (pinfunction "SDO_11") (pintype "bidirectional"))
      (node (ref "U5") (pin "11") (pinfunction "SDO_11") (pintype "bidirectional"))
      (node (ref "U6") (pin "11") (pinfunction "SDO_11") (pintype "bidirectional"))
      (node (ref "U7") (pin "16") (pinfunction "PB4(MISO)_16") (pintype "bidirectional"))
      (node (ref "U8") (pin "2") (pinfunction "MISO_2") (pintype "bidirectional"))
      (node (ref "U9") (pin "2") (pinfunction "MISO_2") (pintype "bidirectional"))
    )
    (net (code "8") (name "MOSI") (class "Default")
      (node (ref "TC1") (pin "P$4") (pinfunction "PIN4_P$4") (pintype "bidirectional"))
      (node (ref "U4") (pin "12") (pinfunction "SDI_12") (pintype "bidirectional"))
      (node (ref "U5") (pin "12") (pinfunction "SDI_12") (pintype "bidirectional"))
      (node (ref "U6") (pin "12") (pinfunction "SDI_12") (pintype "bidirectional"))
      (node (ref "U7") (pin "15") (pinfunction "PB3(MOSI/OC2)_15") (pintype "bidirectional"))
      (node (ref "U8") (pin "3") (pinfunction "MOSI_3") (pintype "input"))
      (node (ref "U9") (pin "5") (pinfunction "MOSI_5") (pintype "bidirectional"))
    )
    (net (code "9") (name "N$2") (class "Default")
      (node (ref "J5") (pin "NEG") (pinfunction "PIN1_NEG") (pintype "bidirectional"))
      (node (ref "R17") (pin "1") (pinfunction "P$1_1") (pintype "passive"))
      (node (ref "U6") (pin "2") (pinfunction "BIAS_2") (pintype "bidirectional"))
    )
    (net (code "10") (name "N$4") (class "Default")
      (node (ref "J4") (pin "NEG") (pinfunction "PIN1_NEG") (pintype "bidirectional"))
      (node (ref "R15") (pin "1") (pinfunction "P$1_1") (pintype "passive"))
      (node (ref "U5") (pin "2") (pinfunction "BIAS_2") (pintype "bidirectional"))
    )
    (net (code "11") (name "N$9") (class "Default")
      (node (ref "J3") (pin "NEG") (pinfunction "PIN1_NEG") (pintype "bidirectional"))
      (node (ref "R13") (pin "1") (pinfunction "P$1_1") (pintype "passive"))
      (node (ref "U4") (pin "2") (pinfunction "BIAS_2") (pintype "bidirectional"))
    )
    (net (code "12") (name "N$33") (class "Default")
      (node (ref "U7") (pin "27") (pinfunction "PC4(ADC4/SDA)_27") (pintype "bidirectional"))
    )
    (net (code "13") (name "N$34") (class "Default")
      (node (ref "U7") (pin "28") (pinfunction "PC5(ADC5/SCL)_28") (pintype "bidirectional"))
    )
    (net (code "14") (name "N$35") (class "Default")
      (node (ref "U7") (pin "19") (pinfunction "ADC6_19") (pintype "bidirectional"))
    )
    (net (code "15") (name "N_SEL1") (class "Default")
      (node (ref "JP1") (pin "2") (pinfunction "2_2") (pintype "passive"))
      (node (ref "U7") (pin "24") (pinfunction "PC1(ADC1)_24") (pintype "bidirectional"))
    )
    (net (code "16") (name "N_SEL2") (class "Default")
      (node (ref "JP2") (pin "2") (pinfunction "2_2") (pintype "passive"))
      (node (ref "U7") (pin "25") (pinfunction "PC2(ADC2)_25") (pintype "bidirectional"))
    )
    (net (code "17") (name "N_SEL3") (class "Default")
      (node (ref "JP3") (pin "2") (pinfunction "2_2") (pintype "passive"))
      (node (ref "U7") (pin "26") (pinfunction "PC3(ADC3)_26") (pintype "bidirectional"))
    )
    (net (code "18") (name "Net-(D5-A)") (class "Default")
      (node (ref "D5") (pin "A-2") (pinfunction "A_A-2") (pintype "passive"))
      (node (ref "L2") (pin "2") (pinfunction "P$2_2") (pintype "passive"))
      (node (ref "U3") (pin "6") (pinfunction "SW_6") (pintype "bidirectional"))
      (node (ref "U3") (pin "7") (pinfunction "SW_7") (pintype "bidirectional"))
    )
    (net (code "19") (name "Net-(D5-C)") (class "Default")
      (node (ref "C13") (pin "2") (pinfunction "2_2") (pintype "passive"))
      (node (ref "C14") (pin "1") (pinfunction "1_1") (pintype "passive"))
      (node (ref "D5") (pin "C-1") (pinfunction "C_C-1") (pintype "passive"))
      (node (ref "J2") (pin "NEG") (pinfunction "PIN1_NEG") (pintype "bidirectional"))
      (node (ref "R11") (pin "2") (pinfunction "P$2_2") (pintype "passive"))
    )
    (net (code "20") (name "Net-(J1-PIN2)") (class "Default")
      (node (ref "D4") (pin "A") (pinfunction "A_A") (pintype "passive"))
      (node (ref "J1") (pin "POS") (pinfunction "PIN2_POS") (pintype "bidirectional"))
    )
    (net (code "21") (name "Net-(J2-PIN2)") (class "Default")
      (node (ref "J2") (pin "POS") (pinfunction "PIN2_POS") (pintype "bidirectional"))
      (node (ref "Q1") (pin "3") (pinfunction "D_3") (pintype "passive"))
    )
    (net (code "22") (name "Net-(J3-PIN2)") (class "Default")
      (node (ref "J3") (pin "POS") (pinfunction "PIN2_POS") (pintype "bidirectional"))
      (node (ref "R14") (pin "1") (pinfunction "P$1_1") (pintype "passive"))
    )
    (net (code "23") (name "Net-(J4-PIN2)") (class "Default")
      (node (ref "J4") (pin "POS") (pinfunction "PIN2_POS") (pintype "bidirectional"))
      (node (ref "R16") (pin "1") (pinfunction "P$1_1") (pintype "passive"))
    )
    (net (code "24") (name "Net-(J5-PIN2)") (class "Default")
      (node (ref "J5") (pin "POS") (pinfunction "PIN2_POS") (pintype "bidirectional"))
      (node (ref "R18") (pin "1") (pinfunction "P$1_1") (pintype "passive"))
    )
    (net (code "25") (name "Net-(J6-DTR)") (class "Default")
      (node (ref "C31") (pin "1") (pinfunction "1_1") (pintype "passive"))
      (node (ref "J6") (pin "1") (pinfunction "DTR_1") (pintype "passive"))
    )
    (net (code "26") (name "Net-(Q2-S)") (class "Default")
      (node (ref "Q2") (pin "2") (pinfunction "S_2") (pintype "passive"))
      (node (ref "R22") (pin "2") (pinfunction "P$2_2") (pintype "passive"))
    )
    (net (code "27") (name "Net-(R1-P$1)") (class "Default")
      (node (ref "D3") (pin "ANODE") (pinfunction "ANODE_ANODE") (pintype "power_in"))
      (node (ref "R1") (pin "1") (pinfunction "P$1_1") (pintype "passive"))
    )
    (net (code "28") (name "Net-(R2-P$1)") (class "Default")
      (node (ref "D2") (pin "ANODE") (pinfunction "ANODE_ANODE") (pintype "power_in"))
      (node (ref "R2") (pin "1") (pinfunction "P$1_1") (pintype "passive"))
    )
    (net (code "29") (name "Net-(R3-P$1)") (class "Default")
      (node (ref "D1") (pin "ANODE") (pinfunction "ANODE_ANODE") (pintype "power_in"))
      (node (ref "R3") (pin "1") (pinfunction "P$1_1") (pintype "passive"))
    )
    (net (code "30") (name "Net-(R4-P$1)") (class "Default")
      (node (ref "R4") (pin "1") (pinfunction "P$1_1") (pintype "passive"))
      (node (ref "R5") (pin "2") (pinfunction "P$2_2") (pintype "passive"))
      (node (ref "U2") (pin "2") (pinfunction "VPCC_2") (pintype "input"))
    )
    (net (code "31") (name "Net-(R6-P$2)") (class "Default")
      (node (ref "R6") (pin "2") (pinfunction "P$2_2") (pintype "passive"))
      (node (ref "U2") (pin "13") (pinfunction "PROG1_13") (pintype "input"))
    )
    (net (code "32") (name "Net-(R7-P$2)") (class "Default")
      (node (ref "R7") (pin "2") (pinfunction "P$2_2") (pintype "passive"))
      (node (ref "U2") (pin "12") (pinfunction "PROG3_12") (pintype "input"))
    )
    (net (code "33") (name "Net-(R8-P$2)") (class "Default")
      (node (ref "R8") (pin "2") (pinfunction "P$2_2") (pintype "passive"))
      (node (ref "U2") (pin "5") (pinfunction "THERM_5") (pintype "input"))
    )
    (net (code "34") (name "Net-(R9-P$1)") (class "Default")
      (node (ref "R9") (pin "1") (pinfunction "P$1_1") (pintype "passive"))
      (node (ref "U3") (pin "9") (pinfunction "CLRES_9") (pintype "bidirectional"))
    )
    (net (code "35") (name "Net-(R10-P$1)") (class "Default")
      (node (ref "C9") (pin "1") (pinfunction "1_1") (pintype "passive"))
      (node (ref "R10") (pin "1") (pinfunction "P$1_1") (pintype "passive"))
    )
    (net (code "36") (name "Net-(R10-P$2)") (class "Default")
      (node (ref "C10") (pin "1") (pinfunction "1_1") (pintype "passive"))
      (node (ref "R10") (pin "2") (pinfunction "P$2_2") (pintype "passive"))
      (node (ref "U3") (pin "1") (pinfunction "COMP_1") (pintype "bidirectional"))
    )
    (net (code "37") (name "Net-(R11-P$1)") (class "Default")
      (node (ref "R11") (pin "1") (pinfunction "P$1_1") (pintype "passive"))
      (node (ref "R12") (pin "2") (pinfunction "P$2_2") (pintype "passive"))
      (node (ref "U3") (pin "2") (pinfunction "FB_2") (pintype "bidirectional"))
    )
    (net (code "38") (name "Net-(R13-P$2)") (class "Default")
      (node (ref "C15") (pin "1") (pinfunction "1_1") (pintype "passive"))
      (node (ref "C16") (pin "2") (pinfunction "2_2") (pintype "passive"))
      (node (ref "R13") (pin "2") (pinfunction "P$2_2") (pintype "passive"))
      (node (ref "U4") (pin "3") (pinfunction "T-_3") (pintype "bidirectional"))
    )
    (net (code "39") (name "Net-(R14-P$2)") (class "Default")
      (node (ref "C16") (pin "1") (pinfunction "1_1") (pintype "passive"))
      (node (ref "C17") (pin "2") (pinfunction "2_2") (pintype "passive"))
      (node (ref "R14") (pin "2") (pinfunction "P$2_2") (pintype "passive"))
      (node (ref "U4") (pin "4") (pinfunction "T+_4") (pintype "bidirectional"))
    )
    (net (code "40") (name "Net-(R15-P$2)") (class "Default")
      (node (ref "C18") (pin "1") (pinfunction "1_1") (pintype "passive"))
      (node (ref "C19") (pin "2") (pinfunction "2_2") (pintype "passive"))
      (node (ref "R15") (pin "2") (pinfunction "P$2_2") (pintype "passive"))
      (node (ref "U5") (pin "3") (pinfunction "T-_3") (pintype "bidirectional"))
    )
    (net (code "41") (name "Net-(R16-P$2)") (class "Default")
      (node (ref "C19") (pin "1") (pinfunction "1_1") (pintype "passive"))
      (node (ref "C20") (pin "2") (pinfunction "2_2") (pintype "passive"))
      (node (ref "R16") (pin "2") (pinfunction "P$2_2") (pintype "passive"))
      (node (ref "U5") (pin "4") (pinfunction "T+_4") (pintype "bidirectional"))
    )
    (net (code "42") (name "Net-(R17-P$2)") (class "Default")
      (node (ref "C25") (pin "1") (pinfunction "1_1") (pintype "passive"))
      (node (ref "C26") (pin "2") (pinfunction "2_2") (pintype "passive"))
      (node (ref "R17") (pin "2") (pinfunction "P$2_2") (pintype "passive"))
      (node (ref "U6") (pin "3") (pinfunction "T-_3") (pintype "bidirectional"))
    )
    (net (code "43") (name "Net-(R18-P$2)") (class "Default")
      (node (ref "C26") (pin "1") (pinfunction "1_1") (pintype "passive"))
      (node (ref "C27") (pin "2") (pinfunction "2_2") (pintype "passive"))
      (node (ref "R18") (pin "2") (pinfunction "P$2_2") (pintype "passive"))
      (node (ref "U6") (pin "4") (pinfunction "T+_4") (pintype "bidirectional"))
    )
    (net (code "44") (name "Net-(R20-P$1)") (class "Default")
      (node (ref "R20") (pin "1") (pinfunction "P$1_1") (pintype "passive"))
      (node (ref "U7") (pin "23") (pinfunction "PC0(ADC0)_23") (pintype "bidirectional"))
    )
    (net (code "45") (name "Net-(R20-P$2)") (class "Default")
      (node (ref "D6") (pin "ANODE") (pinfunction "ANODE_ANODE") (pintype "power_in"))
      (node (ref "R20") (pin "2") (pinfunction "P$2_2") (pintype "passive"))
    )
    (net (code "46") (name "Net-(R21-P$1)") (class "Default")
      (node (ref "R21") (pin "1") (pinfunction "P$1_1") (pintype "passive"))
      (node (ref "U7") (pin "13") (pinfunction "PB1(OC1A)_13") (pintype "bidirectional"))
    )
    (net (code "47") (name "Net-(R21-P$2)") (class "Default")
      (node (ref "D7") (pin "ANODE") (pinfunction "ANODE_ANODE") (pintype "power_in"))
      (node (ref "R21") (pin "2") (pinfunction "P$2_2") (pintype "passive"))
    )
    (net (code "48") (name "Net-(U1-SW1)") (class "Default")
      (node (ref "L1") (pin "P$1") (pinfunction "P$1_P$1") (pintype "passive"))
      (node (ref "U1") (pin "4") (pinfunction "SW1_4") (pintype "bidirectional"))
    )
    (net (code "49") (name "Net-(U1-SW2)") (class "Default")
      (node (ref "L1") (pin "P$2") (pinfunction "P$2_P$2") (pintype "passive"))
      (node (ref "U1") (pin "2") (pinfunction "SW2_2") (pintype "bidirectional"))
    )
    (net (code "50") (name "Net-(U2-STAT1{slash}LBO)") (class "Default")
      (node (ref "D1") (pin "CATHODE") (pinfunction "CATHODE_CATHODE") (pintype "power_in"))
      (node (ref "U2") (pin "8") (pinfunction "STAT1/LBO_8") (pintype "output"))
    )
    (net (code "51") (name "Net-(U2-STAT2)") (class "Default")
      (node (ref "D2") (pin "CATHODE") (pinfunction "CATHODE_CATHODE") (pintype "power_in"))
      (node (ref "U2") (pin "7") (pinfunction "STAT2_7") (pintype "output"))
    )
    (net (code "52") (name "Net-(U2-{slash}PG)") (class "Default")
      (node (ref "D3") (pin "CATHODE") (pinfunction "CATHODE_CATHODE") (pintype "power_in"))
      (node (ref "U2") (pin "6") (pinfunction "/PG_6") (pintype "output"))
    )
    (net (code "53") (name "Net-(U3-SS)") (class "Default")
      (node (ref "C8") (pin "1") (pinfunction "1_1") (pintype "passive"))
      (node (ref "U3") (pin "10") (pinfunction "SS_10") (pintype "bidirectional"))
    )
    (net (code "54") (name "Net-(U7-AREF)") (class "Default")
      (node (ref "C30") (pin "1") (pinfunction "1_1") (pintype "passive"))
      (node (ref "U7") (pin "20") (pinfunction "AREF_20") (pintype "bidirectional"))
    )
    (net (code "55") (name "Net-(U7-PB6(XTAL1{slash}TOSC1))") (class "Default")
      (node (ref "U7") (pin "7") (pinfunction "PB6(XTAL1/TOSC1)_7") (pintype "bidirectional"))
      (node (ref "Y1") (pin "1") (pinfunction "1_1") (pintype "passive"))
    )
    (net (code "56") (name "Net-(U7-PB7(XTAL2{slash}TOSC2))") (class "Default")
      (node (ref "U7") (pin "8") (pinfunction "PB7(XTAL2/TOSC2)_8") (pintype "bidirectional"))
      (node (ref "Y1") (pin "3") (pinfunction "3_3") (pintype "passive"))
    )
    (net (code "57") (name "Net-(U8-ANT)") (class "Default")
      (node (ref "ANT1") (pin "1") (pinfunction "1_1") (pintype "bidirectional"))
      (node (ref "U8") (pin "9") (pinfunction "ANT_9") (pintype "passive"))
    )
    (net (code "58") (name "RF_CS") (class "Default")
      (node (ref "U7") (pin "14") (pinfunction "PB2(SS/OC1B)_14") (pintype "bidirectional"))
      (node (ref "U8") (pin "5") (pinfunction "NSS_5") (pintype "input"))
    )
    (net (code "59") (name "RF_INT") (class "Default")
      (node (ref "U7") (pin "32") (pinfunction "PD2(INT0)_32") (pintype "bidirectional"))
      (node (ref "U8") (pin "14") (pinfunction "DIO0_14") (pintype "bidirectional"))
    )
    (net (code "60") (name "RST") (class "Default")
      (node (ref "C31") (pin "2") (pinfunction "2_2") (pintype "passive"))
      (node (ref "R19") (pin "2") (pinfunction "P$2_2") (pintype "passive"))
      (node (ref "TC1") (pin "P$5") (pinfunction "PIN5_P$5") (pintype "bidirectional"))
      (node (ref "U7") (pin "29") (pinfunction "PC6(/RESET)_29") (pintype "bidirectional"))
    )
    (net (code "61") (name "RX") (class "Default")
      (node (ref "J6") (pin "3") (pinfunction "TXO_3") (pintype "passive"))
      (node (ref "U7") (pin "30") (pinfunction "PD0(RXD)_30") (pintype "bidirectional"))
    )
    (net (code "62") (name "SCK") (class "Default")
      (node (ref "TC1") (pin "P$3") (pinfunction "PIN3_P$3") (pintype "bidirectional"))
      (node (ref "U4") (pin "10") (pinfunction "SCK_10") (pintype "bidirectional"))
      (node (ref "U5") (pin "10") (pinfunction "SCK_10") (pintype "bidirectional"))
      (node (ref "U6") (pin "10") (pinfunction "SCK_10") (pintype "bidirectional"))
      (node (ref "U7") (pin "17") (pinfunction "PB5(SCK)_17") (pintype "bidirectional"))
      (node (ref "U8") (pin "4") (pinfunction "SCK_4") (pintype "input"))
      (node (ref "U9") (pin "6") (pinfunction "CLK_6") (pintype "bidirectional"))
    )
    (net (code "63") (name "TC1_CS") (class "Default")
      (node (ref "U4") (pin "9") (pinfunction "CS_9") (pintype "bidirectional"))
      (node (ref "U7") (pin "11") (pinfunction "PD7(AIN1)_11") (pintype "bidirectional"))
    )
    (net (code "64") (name "TC2_CS") (class "Default")
      (node (ref "U6") (pin "9") (pinfunction "CS_9") (pintype "bidirectional"))
      (node (ref "U7") (pin "10") (pinfunction "PD6(AIN0)_10") (pintype "bidirectional"))
    )
    (net (code "65") (name "TC3_CS") (class "Default")
      (node (ref "U5") (pin "9") (pinfunction "CS_9") (pintype "bidirectional"))
      (node (ref "U7") (pin "9") (pinfunction "PD5(T1)_9") (pintype "bidirectional"))
    )
    (net (code "66") (name "TX") (class "Default")
      (node (ref "J6") (pin "2") (pinfunction "RXI_2") (pintype "passive"))
      (node (ref "U7") (pin "31") (pinfunction "PD1(TXD)_31") (pintype "bidirectional"))
    )
    (net (code "67") (name "V_BAT") (class "Default")
      (node (ref "BATT1") (pin "POS_1") (pinfunction "VBAT_POS_1") (pintype "bidirectional"))
      (node (ref "BATT1") (pin "POS_2") (pinfunction "VBAT_POS_2") (pintype "bidirectional"))
      (node (ref "BATT1") (pin "POS_3") (pinfunction "VBAT_POS_3") (pintype "bidirectional"))
      (node (ref "C1") (pin "1") (pinfunction "1_1") (pintype "passive"))
      (node (ref "C5") (pin "1") (pinfunction "1_1") (pintype "passive"))
      (node (ref "C6") (pin "2") (pinfunction "2_2") (pintype "passive"))
      (node (ref "C7") (pin "1") (pinfunction "1_1") (pintype "passive"))
      (node (ref "L2") (pin "1") (pinfunction "P$1_1") (pintype "passive"))
      (node (ref "Q2") (pin "3") (pinfunction "D_3") (pintype "passive"))
      (node (ref "U1") (pin "5") (pinfunction "PVIN_5") (pintype "bidirectional"))
      (node (ref "U1") (pin "6") (pinfunction "EN_6") (pintype "bidirectional"))
      (node (ref "U1") (pin "8") (pinfunction "VIN_8") (pintype "bidirectional"))
      (node (ref "U2") (pin "14") (pinfunction "VBAT1_14") (pintype "output"))
      (node (ref "U2") (pin "15") (pinfunction "VBAT2_15") (pintype "output"))
      (node (ref "U2") (pin "16") (pinfunction "VBAT3_16") (pintype "output"))
      (node (ref "U3") (pin "8") (pinfunction "VIN_8") (pintype "bidirectional"))
    )
    (net (code "68") (name "V_LOAD") (class "Default")
      (node (ref "C4") (pin "1") (pinfunction "1_1") (pintype "passive"))
      (node (ref "U2") (pin "1") (pinfunction "OUT1_1") (pintype "output"))
      (node (ref "U2") (pin "20") (pinfunction "OUT2_20") (pintype "output"))
    )
    (net (code "69") (name "V_SOLAR") (class "Default")
      (node (ref "C11") (pin "POS") (pinfunction "POS_POS") (pintype "passive"))
      (node (ref "C12") (pin "1") (pinfunction "1_1") (pintype "passive"))
      (node (ref "D4") (pin "C") (pinfunction "C_C") (pintype "passive"))
      (node (ref "R1") (pin "2") (pinfunction "P$2_2") (pintype "passive"))
      (node (ref "R2") (pin "2") (pinfunction "P$2_2") (pintype "passive"))
      (node (ref "R3") (pin "2") (pinfunction "P$2_2") (pintype "passive"))
      (node (ref "R4") (pin "2") (pinfunction "P$2_2") (pintype "passive"))
      (node (ref "U2") (pin "17") (pinfunction "CE_17") (pintype "input"))
      (node (ref "U2") (pin "18") (pinfunction "IN1_18") (pintype "input"))
      (node (ref "U2") (pin "19") (pinfunction "IN2_19") (pintype "input"))
      (node (ref "U2") (pin "3") (pinfunction "SEL_3") (pintype "input"))
      (node (ref "U2") (pin "4") (pinfunction "PROG2_4") (pintype "input"))
      (node (ref "U2") (pin "9") (pinfunction "/TE_9") (pintype "input"))
    )
    (net (code "70") (name "unconnected-(J6-CTS-Pad5)") (class "Default")
      (node (ref "J6") (pin "5") (pinfunction "CTS_5") (pintype "passive"))
    )
    (net (code "71") (name "unconnected-(U4-DNC-Pad6)") (class "Default")
      (node (ref "U4") (pin "6") (pinfunction "DNC_6") (pintype "bidirectional"))
    )
    (net (code "72") (name "unconnected-(U4-DRDY-Pad7)") (class "Default")
      (node (ref "U4") (pin "7") (pinfunction "DRDY_7") (pintype "bidirectional"))
    )
    (net (code "73") (name "unconnected-(U4-FAULT-Pad13)") (class "Default")
      (node (ref "U4") (pin "13") (pinfunction "FAULT_13") (pintype "bidirectional"))
    )
    (net (code "74") (name "unconnected-(U5-DNC-Pad6)") (class "Default")
      (node (ref "U5") (pin "6") (pinfunction "DNC_6") (pintype "bidirectional"))
    )
    (net (code "75") (name "unconnected-(U5-DRDY-Pad7)") (class "Default")
      (node (ref "U5") (pin "7") (pinfunction "DRDY_7") (pintype "bidirectional"))
    )
    (net (code "76") (name "unconnected-(U5-FAULT-Pad13)") (class "Default")
      (node (ref "U5") (pin "13") (pinfunction "FAULT_13") (pintype "bidirectional"))
    )
    (net (code "77") (name "unconnected-(U6-DNC-Pad6)") (class "Default")
      (node (ref "U6") (pin "6") (pinfunction "DNC_6") (pintype "bidirectional"))
    )
    (net (code "78") (name "unconnected-(U6-DRDY-Pad7)") (class "Default")
      (node (ref "U6") (pin "7") (pinfunction "DRDY_7") (pintype "bidirectional"))
    )
    (net (code "79") (name "unconnected-(U6-FAULT-Pad13)") (class "Default")
      (node (ref "U6") (pin "13") (pinfunction "FAULT_13") (pintype "bidirectional"))
    )
    (net (code "80") (name "unconnected-(U8-DIO1-Pad15)") (class "Default")
      (node (ref "U8") (pin "15") (pinfunction "DIO1_15") (pintype "bidirectional"))
    )
    (net (code "81") (name "unconnected-(U8-DIO2-Pad16)") (class "Default")
      (node (ref "U8") (pin "16") (pinfunction "DIO2_16") (pintype "bidirectional"))
    )
    (net (code "82") (name "unconnected-(U8-DIO3-Pad11)") (class "Default")
      (node (ref "U8") (pin "11") (pinfunction "DIO3_11") (pintype "bidirectional"))
    )
    (net (code "83") (name "unconnected-(U8-DIO4-Pad12)") (class "Default")
      (node (ref "U8") (pin "12") (pinfunction "DIO4_12") (pintype "bidirectional"))
    )
    (net (code "84") (name "unconnected-(U8-DIO5-Pad7)") (class "Default")
      (node (ref "U8") (pin "7") (pinfunction "DIO5_7") (pintype "bidirectional"))
    )
    (net (code "85") (name "unconnected-(U8-RESET-Pad6)") (class "Default")
      (node (ref "U8") (pin "6") (pinfunction "RESET_6") (pintype "input"))
    )
  )
)
